# PT4115_LED_Driver.net
KiCad netlist of a schematic drawn in EAGLE
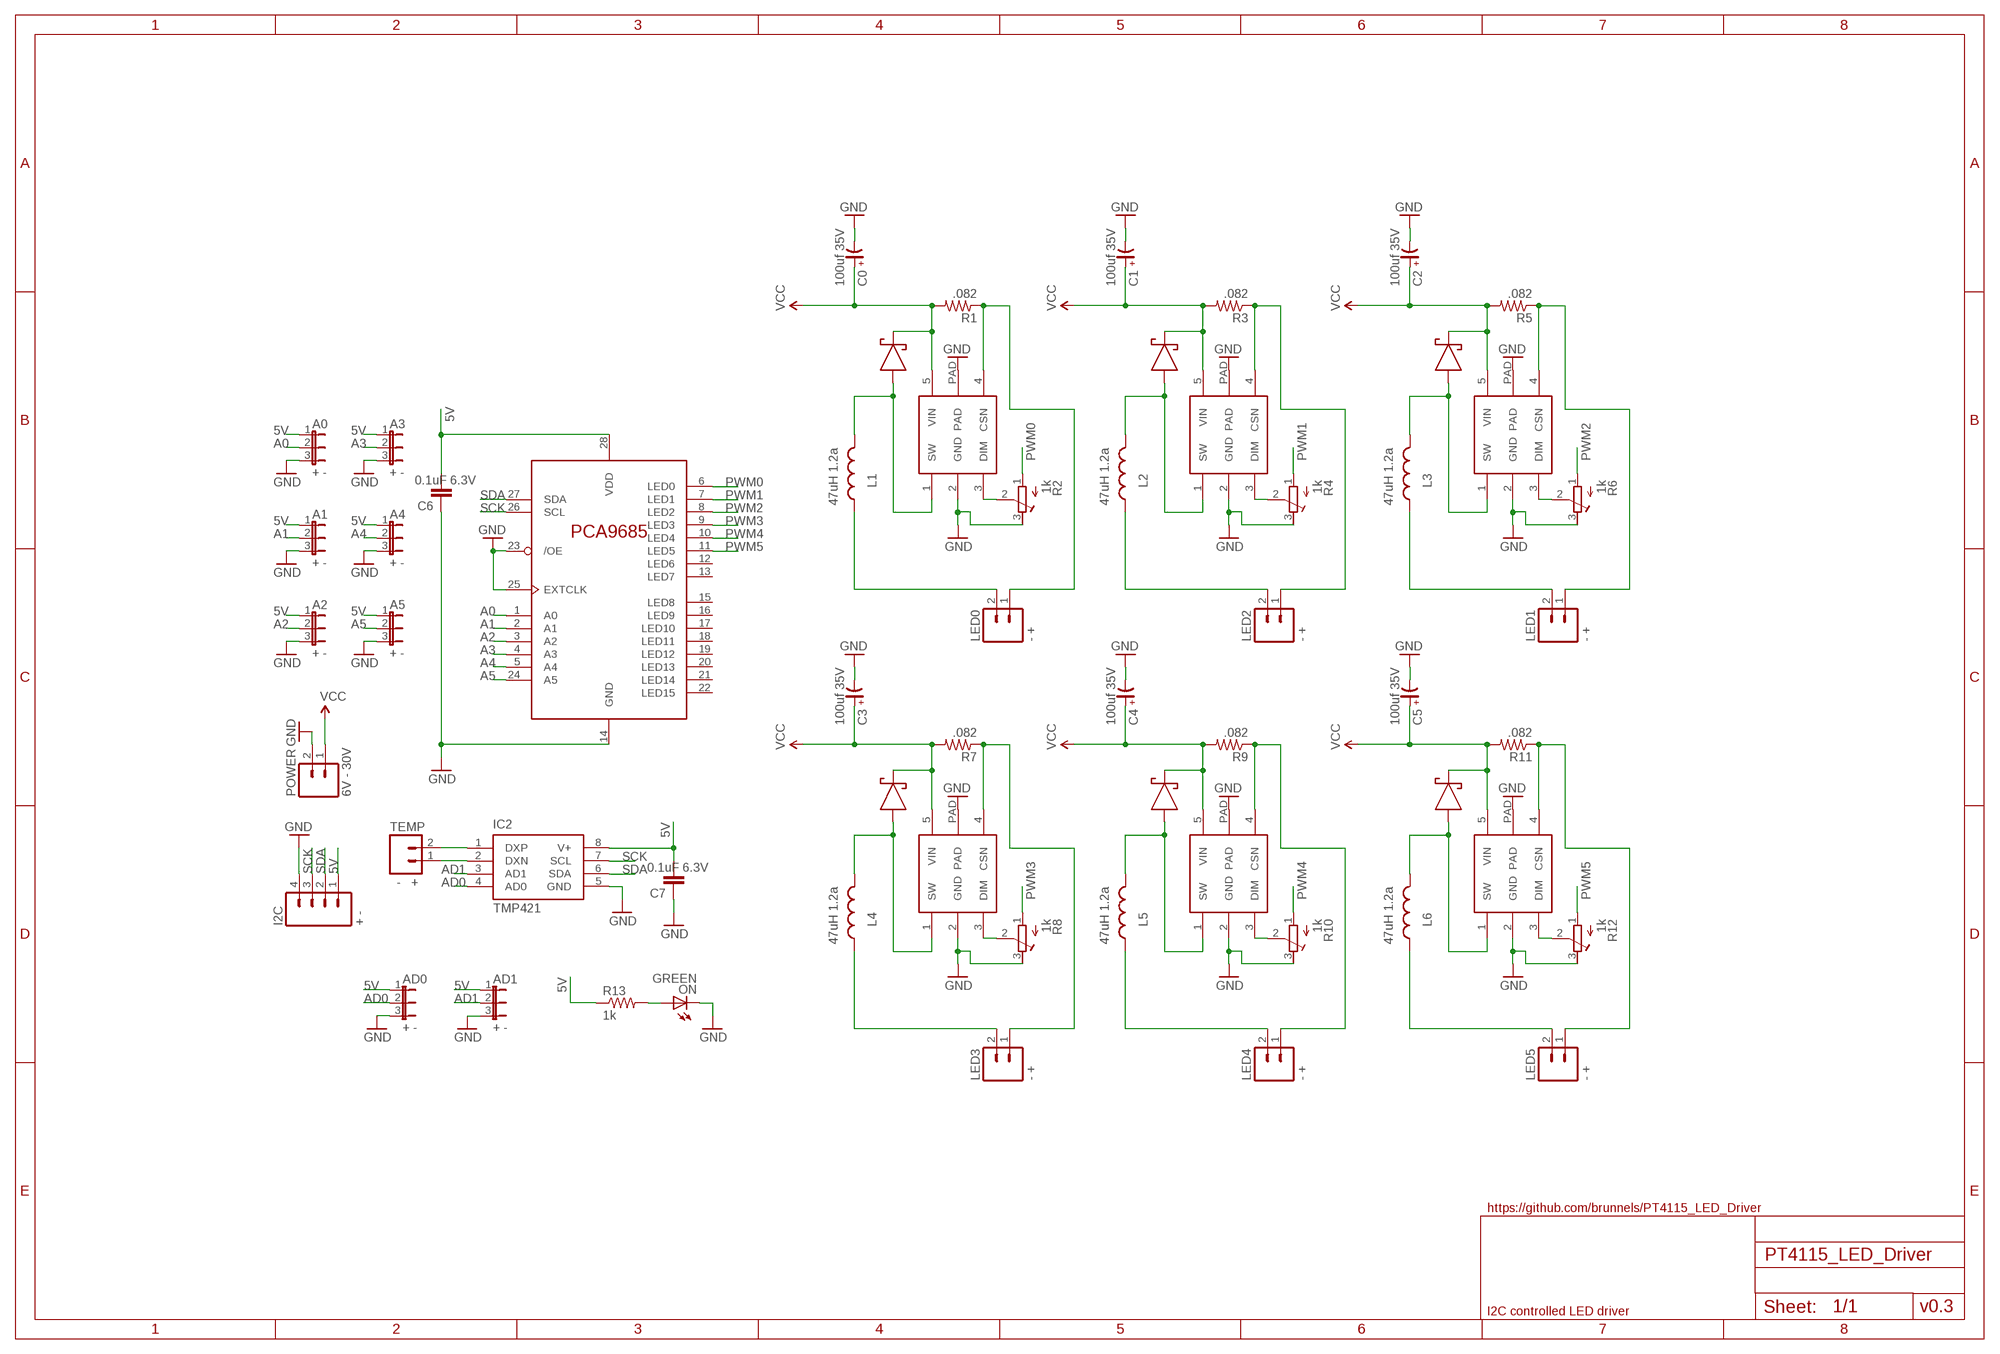
[diagram p0: schematic, sheet 1]

(export (version "E")
  (design (tool "Eeschema 10.0.6"))
  (components
    (comp (ref "A0")
      (value "+ -")
      (footprint "eagle-import:SJ_3")
      (libsource (lib "eagle-import") (part "JUMPER-3SMD"))
    )
    (comp (ref "A1")
      (value "+ -")
      (footprint "eagle-import:SJ_3")
      (libsource (lib "eagle-import") (part "JUMPER-3SMD"))
    )
    (comp (ref "A2")
      (value "+ -")
      (footprint "eagle-import:SJ_3")
      (libsource (lib "eagle-import") (part "JUMPER-3SMD"))
    )
    (comp (ref "A3")
      (value "+ -")
      (footprint "eagle-import:SJ_3")
      (libsource (lib "eagle-import") (part "JUMPER-3SMD"))
    )
    (comp (ref "A4")
      (value "+ -")
      (footprint "eagle-import:SJ_3")
      (libsource (lib "eagle-import") (part "JUMPER-3SMD"))
    )
    (comp (ref "A5")
      (value "+ -")
      (footprint "eagle-import:SJ_3")
      (libsource (lib "eagle-import") (part "JUMPER-3SMD"))
    )
    (comp (ref "AD0")
      (value "+ -")
      (footprint "eagle-import:SJ_3")
      (libsource (lib "eagle-import") (part "JUMPER-3SMD"))
    )
    (comp (ref "AD1")
      (value "+ -")
      (footprint "eagle-import:SJ_3")
      (libsource (lib "eagle-import") (part "JUMPER-3SMD"))
    )
    (comp (ref "C0")
      (value "100uf 35V")
      (footprint "eagle-import:CSV-E_F")
      (libsource (lib "eagle-import") (part "CP_SV-E/F"))
    )
    (comp (ref "C1")
      (value "100uf 35V")
      (footprint "eagle-import:CSV-E_F")
      (libsource (lib "eagle-import") (part "CP_SV-E/F"))
    )
    (comp (ref "C2")
      (value "100uf 35V")
      (footprint "eagle-import:CSV-E_F")
      (libsource (lib "eagle-import") (part "CP_SV-E/F"))
    )
    (comp (ref "C3")
      (value "100uf 35V")
      (footprint "eagle-import:CSV-E_F")
      (libsource (lib "eagle-import") (part "CP_SV-E/F"))
    )
    (comp (ref "C4")
      (value "100uf 35V")
      (footprint "eagle-import:CSV-E_F")
      (libsource (lib "eagle-import") (part "CP_SV-E/F"))
    )
    (comp (ref "C5")
      (value "100uf 35V")
      (footprint "eagle-import:CSV-E_F")
      (libsource (lib "eagle-import") (part "CP_SV-E/F"))
    )
    (comp (ref "C6")
      (value "0.1uF 6.3V")
      (footprint "eagle-import:0805")
      (libsource (lib "eagle-import") (part "CAP0805"))
    )
    (comp (ref "C7")
      (value "0.1uF 6.3V")
      (footprint "eagle-import:0805")
      (libsource (lib "eagle-import") (part "CAP0805"))
    )
    (comp (ref "D1")
      (value "SCHOTTKY_DIODE-SS18")
      (footprint "eagle-import:DO-214")
      (libsource (lib "eagle-import") (part "SCHOTTKY_DIODE-SS18"))
    )
    (comp (ref "D2")
      (value "SCHOTTKY_DIODE-SS18")
      (footprint "eagle-import:DO-214")
      (libsource (lib "eagle-import") (part "SCHOTTKY_DIODE-SS18"))
    )
    (comp (ref "D3")
      (value "SCHOTTKY_DIODE-SS18")
      (footprint "eagle-import:DO-214")
      (libsource (lib "eagle-import") (part "SCHOTTKY_DIODE-SS18"))
    )
    (comp (ref "D4")
      (value "SCHOTTKY_DIODE-SS18")
      (footprint "eagle-import:DO-214")
      (libsource (lib "eagle-import") (part "SCHOTTKY_DIODE-SS18"))
    )
    (comp (ref "D5")
      (value "SCHOTTKY_DIODE-SS18")
      (footprint "eagle-import:DO-214")
      (libsource (lib "eagle-import") (part "SCHOTTKY_DIODE-SS18"))
    )
    (comp (ref "D6")
      (value "SCHOTTKY_DIODE-SS18")
      (footprint "eagle-import:DO-214")
      (libsource (lib "eagle-import") (part "SCHOTTKY_DIODE-SS18"))
    )
    (comp (ref "DRV0")
      (value "PT4115")
      (footprint "eagle-import:SOT89-5")
      (libsource (lib "eagle-import") (part "PT4115"))
    )
    (comp (ref "DRV1")
      (value "PT4115")
      (footprint "eagle-import:SOT89-5")
      (libsource (lib "eagle-import") (part "PT4115"))
    )
    (comp (ref "DRV2")
      (value "PT4115")
      (footprint "eagle-import:SOT89-5")
      (libsource (lib "eagle-import") (part "PT4115"))
    )
    (comp (ref "DRV3")
      (value "PT4115")
      (footprint "eagle-import:SOT89-5")
      (libsource (lib "eagle-import") (part "PT4115"))
    )
    (comp (ref "DRV4")
      (value "PT4115")
      (footprint "eagle-import:SOT89-5")
      (libsource (lib "eagle-import") (part "PT4115"))
    )
    (comp (ref "DRV5")
      (value "PT4115")
      (footprint "eagle-import:SOT89-5")
      (libsource (lib "eagle-import") (part "PT4115"))
    )
    (comp (ref "I2C")
      (value "+ -")
      (footprint "eagle-import:MOLEX-1X4")
      (libsource (lib "eagle-import") (part "M04POLAR"))
    )
    (comp (ref "IC1")
      (value "PCA9685PW")
      (footprint "eagle-import:TSSOP28")
      (libsource (lib "eagle-import") (part "PCA9685PW"))
    )
    (comp (ref "IC2")
      (value "TMP421")
      (footprint "eagle-import:SOT23-8")
      (libsource (lib "eagle-import") (part "TMP421"))
    )
    (comp (ref "L1")
      (value "47uH 1.2a")
      (footprint "eagle-import:CR54")
      (libsource (lib "eagle-import") (part "INDUCTORCR54"))
    )
    (comp (ref "L2")
      (value "47uH 1.2a")
      (footprint "eagle-import:CR54")
      (libsource (lib "eagle-import") (part "INDUCTORCR54"))
    )
    (comp (ref "L3")
      (value "47uH 1.2a")
      (footprint "eagle-import:CR54")
      (libsource (lib "eagle-import") (part "INDUCTORCR54"))
    )
    (comp (ref "L4")
      (value "47uH 1.2a")
      (footprint "eagle-import:CR54")
      (libsource (lib "eagle-import") (part "INDUCTORCR54"))
    )
    (comp (ref "L5")
      (value "47uH 1.2a")
      (footprint "eagle-import:CR54")
      (libsource (lib "eagle-import") (part "INDUCTORCR54"))
    )
    (comp (ref "L6")
      (value "47uH 1.2a")
      (footprint "eagle-import:CR54")
      (libsource (lib "eagle-import") (part "INDUCTORCR54"))
    )
    (comp (ref "LED0")
      (value "- +")
      (footprint "eagle-import:SCREWTERMINAL-3.5MM-2")
      (libsource (lib "eagle-import") (part "M023.5MM"))
    )
    (comp (ref "LED1")
      (value "- +")
      (footprint "eagle-import:SCREWTERMINAL-3.5MM-2")
      (libsource (lib "eagle-import") (part "M023.5MM"))
    )
    (comp (ref "LED2")
      (value "- +")
      (footprint "eagle-import:SCREWTERMINAL-3.5MM-2")
      (libsource (lib "eagle-import") (part "M023.5MM"))
    )
    (comp (ref "LED3")
      (value "- +")
      (footprint "eagle-import:SCREWTERMINAL-3.5MM-2")
      (libsource (lib "eagle-import") (part "M023.5MM"))
    )
    (comp (ref "LED4")
      (value "- +")
      (footprint "eagle-import:SCREWTERMINAL-3.5MM-2")
      (libsource (lib "eagle-import") (part "M023.5MM"))
    )
    (comp (ref "LED5")
      (value "- +")
      (footprint "eagle-import:SCREWTERMINAL-3.5MM-2")
      (libsource (lib "eagle-import") (part "M023.5MM"))
    )
    (comp (ref "ON")
      (value "GREEN")
      (footprint "eagle-import:CHIPLED_0805")
      (libsource (lib "eagle-import") (part "LEDCHIPLED_0805"))
    )
    (comp (ref "POWER")
      (value "6V - 30V")
      (footprint "eagle-import:SCREWTERMINAL-3.5MM-2")
      (libsource (lib "eagle-import") (part "M023.5MM"))
    )
    (comp (ref "R1")
      (value ".082")
      (footprint "eagle-import:1206")
      (libsource (lib "eagle-import") (part "RESISTOR1206"))
    )
    (comp (ref "R2")
      (value "1k")
      (footprint "eagle-import:RTRIM3296W")
      (libsource (lib "eagle-import") (part "R-TRIMM3296W"))
    )
    (comp (ref "R3")
      (value ".082")
      (footprint "eagle-import:1206")
      (libsource (lib "eagle-import") (part "RESISTOR1206"))
    )
    (comp (ref "R4")
      (value "1k")
      (footprint "eagle-import:RTRIM3296W")
      (libsource (lib "eagle-import") (part "R-TRIMM3296W"))
    )
    (comp (ref "R5")
      (value ".082")
      (footprint "eagle-import:1206")
      (libsource (lib "eagle-import") (part "RESISTOR1206"))
    )
    (comp (ref "R6")
      (value "1k")
      (footprint "eagle-import:RTRIM3296W")
      (libsource (lib "eagle-import") (part "R-TRIMM3296W"))
    )
    (comp (ref "R7")
      (value ".082")
      (footprint "eagle-import:1206")
      (libsource (lib "eagle-import") (part "RESISTOR1206"))
    )
    (comp (ref "R8")
      (value "1k")
      (footprint "eagle-import:RTRIM3296W")
      (libsource (lib "eagle-import") (part "R-TRIMM3296W"))
    )
    (comp (ref "R9")
      (value ".082")
      (footprint "eagle-import:1206")
      (libsource (lib "eagle-import") (part "RESISTOR1206"))
    )
    (comp (ref "R10")
      (value "1k")
      (footprint "eagle-import:RTRIM3296W")
      (libsource (lib "eagle-import") (part "R-TRIMM3296W"))
    )
    (comp (ref "R11")
      (value ".082")
      (footprint "eagle-import:1206")
      (libsource (lib "eagle-import") (part "RESISTOR1206"))
    )
    (comp (ref "R12")
      (value "1k")
      (footprint "eagle-import:RTRIM3296W")
      (libsource (lib "eagle-import") (part "R-TRIMM3296W"))
    )
    (comp (ref "R13")
      (value "1k")
      (footprint "eagle-import:0603-RES")
      (libsource (lib "eagle-import") (part "SparkFun_RESISTOR0603-RES"))
    )
    (comp (ref "TEMP")
      (value "- +")
      (footprint "eagle-import:1X02")
      (libsource (lib "eagle-import") (part "M02PTH"))
    )
  )
  (nets
    (net (code "1") (name "/5V") (class "Default")
      (node (ref "A0") (pin "1") (pinfunction "1_1") (pintype "passive"))
      (node (ref "A1") (pin "1") (pinfunction "1_1") (pintype "passive"))
      (node (ref "A2") (pin "1") (pinfunction "1_1") (pintype "passive"))
      (node (ref "A3") (pin "1") (pinfunction "1_1") (pintype "passive"))
      (node (ref "A4") (pin "1") (pinfunction "1_1") (pintype "passive"))
      (node (ref "A5") (pin "1") (pinfunction "1_1") (pintype "passive"))
      (node (ref "AD0") (pin "1") (pinfunction "1_1") (pintype "passive"))
      (node (ref "AD1") (pin "1") (pinfunction "1_1") (pintype "passive"))
      (node (ref "C6") (pin "2") (pinfunction "2_2") (pintype "passive"))
      (node (ref "C7") (pin "2") (pinfunction "2_2") (pintype "passive"))
      (node (ref "I2C") (pin "1") (pinfunction "1_1") (pintype "passive"))
      (node (ref "IC1") (pin "28") (pinfunction "VDD_28") (pintype "power_in"))
      (node (ref "IC2") (pin "8") (pinfunction "V+_8") (pintype "bidirectional"))
      (node (ref "R13") (pin "1") (pinfunction "1_1") (pintype "passive"))
    )
    (net (code "2") (name "/A0") (class "Default")
      (node (ref "A0") (pin "2") (pinfunction "2_2") (pintype "passive"))
      (node (ref "IC1") (pin "1") (pinfunction "A0_1") (pintype "bidirectional"))
    )
    (net (code "3") (name "/A1") (class "Default")
      (node (ref "A1") (pin "2") (pinfunction "2_2") (pintype "passive"))
      (node (ref "IC1") (pin "2") (pinfunction "A1_2") (pintype "bidirectional"))
    )
    (net (code "4") (name "/A2") (class "Default")
      (node (ref "A2") (pin "2") (pinfunction "2_2") (pintype "passive"))
      (node (ref "IC1") (pin "3") (pinfunction "A2_3") (pintype "bidirectional"))
    )
    (net (code "5") (name "/A3") (class "Default")
      (node (ref "A3") (pin "2") (pinfunction "2_2") (pintype "passive"))
      (node (ref "IC1") (pin "4") (pinfunction "A3_4") (pintype "bidirectional"))
    )
    (net (code "6") (name "/A4") (class "Default")
      (node (ref "A4") (pin "2") (pinfunction "2_2") (pintype "passive"))
      (node (ref "IC1") (pin "5") (pinfunction "A4_5") (pintype "bidirectional"))
    )
    (net (code "7") (name "/A5") (class "Default")
      (node (ref "A5") (pin "2") (pinfunction "2_2") (pintype "passive"))
      (node (ref "IC1") (pin "24") (pinfunction "A5_24") (pintype "bidirectional"))
    )
    (net (code "8") (name "/AD0") (class "Default")
      (node (ref "AD0") (pin "2") (pinfunction "2_2") (pintype "passive"))
      (node (ref "IC2") (pin "4") (pinfunction "AD0_4") (pintype "bidirectional"))
    )
    (net (code "9") (name "/AD1") (class "Default")
      (node (ref "AD1") (pin "2") (pinfunction "2_2") (pintype "passive"))
      (node (ref "IC2") (pin "3") (pinfunction "AD1_3") (pintype "bidirectional"))
    )
    (net (code "10") (name "/PWM0") (class "Default")
      (node (ref "IC1") (pin "6") (pinfunction "LED0_6") (pintype "bidirectional"))
      (node (ref "R2") (pin "1") (pinfunction "E_1") (pintype "passive"))
    )
    (net (code "11") (name "/PWM1") (class "Default")
      (node (ref "IC1") (pin "7") (pinfunction "LED1_7") (pintype "bidirectional"))
      (node (ref "R4") (pin "1") (pinfunction "E_1") (pintype "passive"))
    )
    (net (code "12") (name "/PWM2") (class "Default")
      (node (ref "IC1") (pin "8") (pinfunction "LED2_8") (pintype "bidirectional"))
      (node (ref "R6") (pin "1") (pinfunction "E_1") (pintype "passive"))
    )
    (net (code "13") (name "/PWM3") (class "Default")
      (node (ref "IC1") (pin "9") (pinfunction "LED3_9") (pintype "bidirectional"))
      (node (ref "R8") (pin "1") (pinfunction "E_1") (pintype "passive"))
    )
    (net (code "14") (name "/PWM4") (class "Default")
      (node (ref "IC1") (pin "10") (pinfunction "LED4_10") (pintype "bidirectional"))
      (node (ref "R10") (pin "1") (pinfunction "E_1") (pintype "passive"))
    )
    (net (code "15") (name "/PWM5") (class "Default")
      (node (ref "IC1") (pin "11") (pinfunction "LED5_11") (pintype "bidirectional"))
      (node (ref "R12") (pin "1") (pinfunction "E_1") (pintype "passive"))
    )
    (net (code "16") (name "/SCK") (class "Default")
      (node (ref "I2C") (pin "3") (pinfunction "3_3") (pintype "passive"))
      (node (ref "IC1") (pin "26") (pinfunction "SCL_26") (pintype "bidirectional"))
      (node (ref "IC2") (pin "7") (pinfunction "SCL_7") (pintype "bidirectional"))
    )
    (net (code "17") (name "/SDA") (class "Default")
      (node (ref "I2C") (pin "2") (pinfunction "2_2") (pintype "passive"))
      (node (ref "IC1") (pin "27") (pinfunction "SDA_27") (pintype "bidirectional"))
      (node (ref "IC2") (pin "6") (pinfunction "SDA_6") (pintype "bidirectional"))
    )
    (net (code "18") (name "GND") (class "Default")
      (node (ref "A0") (pin "3") (pinfunction "3_3") (pintype "passive"))
      (node (ref "A1") (pin "3") (pinfunction "3_3") (pintype "passive"))
      (node (ref "A2") (pin "3") (pinfunction "3_3") (pintype "passive"))
      (node (ref "A3") (pin "3") (pinfunction "3_3") (pintype "passive"))
      (node (ref "A4") (pin "3") (pinfunction "3_3") (pintype "passive"))
      (node (ref "A5") (pin "3") (pinfunction "3_3") (pintype "passive"))
      (node (ref "AD0") (pin "3") (pinfunction "3_3") (pintype "passive"))
      (node (ref "AD1") (pin "3") (pinfunction "3_3") (pintype "passive"))
      (node (ref "C0") (pin "-") (pinfunction "-_-") (pintype "passive"))
      (node (ref "C1") (pin "-") (pinfunction "-_-") (pintype "passive"))
      (node (ref "C2") (pin "-") (pinfunction "-_-") (pintype "passive"))
      (node (ref "C3") (pin "-") (pinfunction "-_-") (pintype "passive"))
      (node (ref "C4") (pin "-") (pinfunction "-_-") (pintype "passive"))
      (node (ref "C5") (pin "-") (pinfunction "-_-") (pintype "passive"))
      (node (ref "C6") (pin "1") (pinfunction "1_1") (pintype "passive"))
      (node (ref "C7") (pin "1") (pinfunction "1_1") (pintype "passive"))
      (node (ref "DRV0") (pin "2") (pinfunction "GND_2") (pintype "bidirectional"))
      (node (ref "DRV0") (pin "PAD") (pinfunction "PAD_PAD") (pintype "bidirectional"))
      (node (ref "DRV1") (pin "2") (pinfunction "GND_2") (pintype "bidirectional"))
      (node (ref "DRV1") (pin "PAD") (pinfunction "PAD_PAD") (pintype "bidirectional"))
      (node (ref "DRV2") (pin "2") (pinfunction "GND_2") (pintype "bidirectional"))
      (node (ref "DRV2") (pin "PAD") (pinfunction "PAD_PAD") (pintype "bidirectional"))
      (node (ref "DRV3") (pin "2") (pinfunction "GND_2") (pintype "bidirectional"))
      (node (ref "DRV3") (pin "PAD") (pinfunction "PAD_PAD") (pintype "bidirectional"))
      (node (ref "DRV4") (pin "2") (pinfunction "GND_2") (pintype "bidirectional"))
      (node (ref "DRV4") (pin "PAD") (pinfunction "PAD_PAD") (pintype "bidirectional"))
      (node (ref "DRV5") (pin "2") (pinfunction "GND_2") (pintype "bidirectional"))
      (node (ref "DRV5") (pin "PAD") (pinfunction "PAD_PAD") (pintype "bidirectional"))
      (node (ref "I2C") (pin "4") (pinfunction "4_4") (pintype "passive"))
      (node (ref "IC1") (pin "14") (pinfunction "GND_14") (pintype "power_in"))
      (node (ref "IC1") (pin "23") (pinfunction "/OE_23") (pintype "bidirectional"))
      (node (ref "IC1") (pin "25") (pinfunction "EXTCLK_25") (pintype "input"))
      (node (ref "IC2") (pin "5") (pinfunction "GND_5") (pintype "bidirectional"))
      (node (ref "ON") (pin "C") (pinfunction "C_C") (pintype "passive"))
      (node (ref "POWER") (pin "2") (pinfunction "2_2") (pintype "passive"))
      (node (ref "R10") (pin "3") (pinfunction "A_3") (pintype "passive"))
      (node (ref "R12") (pin "3") (pinfunction "A_3") (pintype "passive"))
      (node (ref "R2") (pin "3") (pinfunction "A_3") (pintype "passive"))
      (node (ref "R4") (pin "3") (pinfunction "A_3") (pintype "passive"))
      (node (ref "R6") (pin "3") (pinfunction "A_3") (pintype "passive"))
      (node (ref "R8") (pin "3") (pinfunction "A_3") (pintype "passive"))
    )
    (net (code "19") (name "Net-(D1-ANODE)") (class "Default")
      (node (ref "D1") (pin "P$2") (pinfunction "ANODE_P$2") (pintype "bidirectional"))
      (node (ref "DRV1") (pin "1") (pinfunction "SW_1") (pintype "bidirectional"))
      (node (ref "L2") (pin "P$2") (pinfunction "2_P$2") (pintype "passive"))
    )
    (net (code "20") (name "Net-(D2-ANODE)") (class "Default")
      (node (ref "D2") (pin "P$2") (pinfunction "ANODE_P$2") (pintype "bidirectional"))
      (node (ref "DRV2") (pin "1") (pinfunction "SW_1") (pintype "bidirectional"))
      (node (ref "L3") (pin "P$2") (pinfunction "2_P$2") (pintype "passive"))
    )
    (net (code "21") (name "Net-(D3-ANODE)") (class "Default")
      (node (ref "D3") (pin "P$2") (pinfunction "ANODE_P$2") (pintype "bidirectional"))
      (node (ref "DRV0") (pin "1") (pinfunction "SW_1") (pintype "bidirectional"))
      (node (ref "L1") (pin "P$2") (pinfunction "2_P$2") (pintype "passive"))
    )
    (net (code "22") (name "Net-(D4-ANODE)") (class "Default")
      (node (ref "D4") (pin "P$2") (pinfunction "ANODE_P$2") (pintype "bidirectional"))
      (node (ref "DRV3") (pin "1") (pinfunction "SW_1") (pintype "bidirectional"))
      (node (ref "L4") (pin "P$2") (pinfunction "2_P$2") (pintype "passive"))
    )
    (net (code "23") (name "Net-(D5-ANODE)") (class "Default")
      (node (ref "D5") (pin "P$2") (pinfunction "ANODE_P$2") (pintype "bidirectional"))
      (node (ref "DRV4") (pin "1") (pinfunction "SW_1") (pintype "bidirectional"))
      (node (ref "L5") (pin "P$2") (pinfunction "2_P$2") (pintype "passive"))
    )
    (net (code "24") (name "Net-(D6-ANODE)") (class "Default")
      (node (ref "D6") (pin "P$2") (pinfunction "ANODE_P$2") (pintype "bidirectional"))
      (node (ref "DRV5") (pin "1") (pinfunction "SW_1") (pintype "bidirectional"))
      (node (ref "L6") (pin "P$2") (pinfunction "2_P$2") (pintype "passive"))
    )
    (net (code "25") (name "Net-(DRV0-CSN)") (class "Default")
      (node (ref "DRV0") (pin "4") (pinfunction "CSN_4") (pintype "bidirectional"))
      (node (ref "LED0") (pin "1") (pinfunction "1_1") (pintype "passive"))
      (node (ref "R1") (pin "1") (pinfunction "1_1") (pintype "passive"))
    )
    (net (code "26") (name "Net-(DRV0-DIM)") (class "Default")
      (node (ref "DRV0") (pin "3") (pinfunction "DIM_3") (pintype "bidirectional"))
      (node (ref "R2") (pin "2") (pinfunction "S_2") (pintype "passive"))
    )
    (net (code "27") (name "Net-(DRV1-CSN)") (class "Default")
      (node (ref "DRV1") (pin "4") (pinfunction "CSN_4") (pintype "bidirectional"))
      (node (ref "LED2") (pin "1") (pinfunction "1_1") (pintype "passive"))
      (node (ref "R3") (pin "1") (pinfunction "1_1") (pintype "passive"))
    )
    (net (code "28") (name "Net-(DRV1-DIM)") (class "Default")
      (node (ref "DRV1") (pin "3") (pinfunction "DIM_3") (pintype "bidirectional"))
      (node (ref "R4") (pin "2") (pinfunction "S_2") (pintype "passive"))
    )
    (net (code "29") (name "Net-(DRV2-CSN)") (class "Default")
      (node (ref "DRV2") (pin "4") (pinfunction "CSN_4") (pintype "bidirectional"))
      (node (ref "LED1") (pin "1") (pinfunction "1_1") (pintype "passive"))
      (node (ref "R5") (pin "1") (pinfunction "1_1") (pintype "passive"))
    )
    (net (code "30") (name "Net-(DRV2-DIM)") (class "Default")
      (node (ref "DRV2") (pin "3") (pinfunction "DIM_3") (pintype "bidirectional"))
      (node (ref "R6") (pin "2") (pinfunction "S_2") (pintype "passive"))
    )
    (net (code "31") (name "Net-(DRV3-CSN)") (class "Default")
      (node (ref "DRV3") (pin "4") (pinfunction "CSN_4") (pintype "bidirectional"))
      (node (ref "LED3") (pin "1") (pinfunction "1_1") (pintype "passive"))
      (node (ref "R7") (pin "1") (pinfunction "1_1") (pintype "passive"))
    )
    (net (code "32") (name "Net-(DRV3-DIM)") (class "Default")
      (node (ref "DRV3") (pin "3") (pinfunction "DIM_3") (pintype "bidirectional"))
      (node (ref "R8") (pin "2") (pinfunction "S_2") (pintype "passive"))
    )
    (net (code "33") (name "Net-(DRV4-CSN)") (class "Default")
      (node (ref "DRV4") (pin "4") (pinfunction "CSN_4") (pintype "bidirectional"))
      (node (ref "LED4") (pin "1") (pinfunction "1_1") (pintype "passive"))
      (node (ref "R9") (pin "1") (pinfunction "1_1") (pintype "passive"))
    )
    (net (code "34") (name "Net-(DRV4-DIM)") (class "Default")
      (node (ref "DRV4") (pin "3") (pinfunction "DIM_3") (pintype "bidirectional"))
      (node (ref "R10") (pin "2") (pinfunction "S_2") (pintype "passive"))
    )
    (net (code "35") (name "Net-(DRV5-CSN)") (class "Default")
      (node (ref "DRV5") (pin "4") (pinfunction "CSN_4") (pintype "bidirectional"))
      (node (ref "LED5") (pin "1") (pinfunction "1_1") (pintype "passive"))
      (node (ref "R11") (pin "1") (pinfunction "1_1") (pintype "passive"))
    )
    (net (code "36") (name "Net-(DRV5-DIM)") (class "Default")
      (node (ref "DRV5") (pin "3") (pinfunction "DIM_3") (pintype "bidirectional"))
      (node (ref "R12") (pin "2") (pinfunction "S_2") (pintype "passive"))
    )
    (net (code "37") (name "Net-(IC2-DXN)") (class "Default")
      (node (ref "IC2") (pin "2") (pinfunction "DXN_2") (pintype "bidirectional"))
      (node (ref "TEMP") (pin "1") (pinfunction "1_1") (pintype "passive"))
    )
    (net (code "38") (name "Net-(IC2-DXP)") (class "Default")
      (node (ref "IC2") (pin "1") (pinfunction "DXP_1") (pintype "bidirectional"))
      (node (ref "TEMP") (pin "2") (pinfunction "2_2") (pintype "passive"))
    )
    (net (code "39") (name "Net-(L1-1)") (class "Default")
      (node (ref "L1") (pin "P$1") (pinfunction "1_P$1") (pintype "passive"))
      (node (ref "LED0") (pin "2") (pinfunction "2_2") (pintype "passive"))
    )
    (net (code "40") (name "Net-(L2-1)") (class "Default")
      (node (ref "L2") (pin "P$1") (pinfunction "1_P$1") (pintype "passive"))
      (node (ref "LED2") (pin "2") (pinfunction "2_2") (pintype "passive"))
    )
    (net (code "41") (name "Net-(L3-1)") (class "Default")
      (node (ref "L3") (pin "P$1") (pinfunction "1_P$1") (pintype "passive"))
      (node (ref "LED1") (pin "2") (pinfunction "2_2") (pintype "passive"))
    )
    (net (code "42") (name "Net-(L4-1)") (class "Default")
      (node (ref "L4") (pin "P$1") (pinfunction "1_P$1") (pintype "passive"))
      (node (ref "LED3") (pin "2") (pinfunction "2_2") (pintype "passive"))
    )
    (net (code "43") (name "Net-(L5-1)") (class "Default")
      (node (ref "L5") (pin "P$1") (pinfunction "1_P$1") (pintype "passive"))
      (node (ref "LED4") (pin "2") (pinfunction "2_2") (pintype "passive"))
    )
    (net (code "44") (name "Net-(L6-1)") (class "Default")
      (node (ref "L6") (pin "P$1") (pinfunction "1_P$1") (pintype "passive"))
      (node (ref "LED5") (pin "2") (pinfunction "2_2") (pintype "passive"))
    )
    (net (code "45") (name "Net-(ON-PadA)") (class "Default")
      (node (ref "ON") (pin "A") (pinfunction "A_A") (pintype "passive"))
      (node (ref "R13") (pin "2") (pinfunction "2_2") (pintype "passive"))
    )
    (net (code "46") (name "VCC") (class "Default")
      (node (ref "C0") (pin "+") (pinfunction "+_+") (pintype "passive"))
      (node (ref "C1") (pin "+") (pinfunction "+_+") (pintype "passive"))
      (node (ref "C2") (pin "+") (pinfunction "+_+") (pintype "passive"))
      (node (ref "C3") (pin "+") (pinfunction "+_+") (pintype "passive"))
      (node (ref "C4") (pin "+") (pinfunction "+_+") (pintype "passive"))
      (node (ref "C5") (pin "+") (pinfunction "+_+") (pintype "passive"))
      (node (ref "D1") (pin "P$1") (pinfunction "CATHODE_P$1") (pintype "bidirectional"))
      (node (ref "D2") (pin "P$1") (pinfunction "CATHODE_P$1") (pintype "bidirectional"))
      (node (ref "D3") (pin "P$1") (pinfunction "CATHODE_P$1") (pintype "bidirectional"))
      (node (ref "D4") (pin "P$1") (pinfunction "CATHODE_P$1") (pintype "bidirectional"))
      (node (ref "D5") (pin "P$1") (pinfunction "CATHODE_P$1") (pintype "bidirectional"))
      (node (ref "D6") (pin "P$1") (pinfunction "CATHODE_P$1") (pintype "bidirectional"))
      (node (ref "DRV0") (pin "5") (pinfunction "VIN_5") (pintype "bidirectional"))
      (node (ref "DRV1") (pin "5") (pinfunction "VIN_5") (pintype "bidirectional"))
      (node (ref "DRV2") (pin "5") (pinfunction "VIN_5") (pintype "bidirectional"))
      (node (ref "DRV3") (pin "5") (pinfunction "VIN_5") (pintype "bidirectional"))
      (node (ref "DRV4") (pin "5") (pinfunction "VIN_5") (pintype "bidirectional"))
      (node (ref "DRV5") (pin "5") (pinfunction "VIN_5") (pintype "bidirectional"))
      (node (ref "POWER") (pin "1") (pinfunction "1_1") (pintype "passive"))
      (node (ref "R1") (pin "2") (pinfunction "2_2") (pintype "passive"))
      (node (ref "R11") (pin "2") (pinfunction "2_2") (pintype "passive"))
      (node (ref "R3") (pin "2") (pinfunction "2_2") (pintype "passive"))
      (node (ref "R5") (pin "2") (pinfunction "2_2") (pintype "passive"))
      (node (ref "R7") (pin "2") (pinfunction "2_2") (pintype "passive"))
      (node (ref "R9") (pin "2") (pinfunction "2_2") (pintype "passive"))
    )
    (net (code "47") (name "unconnected-(IC1-LED6-Pad12)") (class "Default")
      (node (ref "IC1") (pin "12") (pinfunction "LED6_12") (pintype "bidirectional"))
    )
    (net (code "48") (name "unconnected-(IC1-LED7-Pad13)") (class "Default")
      (node (ref "IC1") (pin "13") (pinfunction "LED7_13") (pintype "bidirectional"))
    )
    (net (code "49") (name "unconnected-(IC1-LED8-Pad15)") (class "Default")
      (node (ref "IC1") (pin "15") (pinfunction "LED8_15") (pintype "bidirectional"))
    )
    (net (code "50") (name "unconnected-(IC1-LED9-Pad16)") (class "Default")
      (node (ref "IC1") (pin "16") (pinfunction "LED9_16") (pintype "bidirectional"))
    )
    (net (code "51") (name "unconnected-(IC1-LED10-Pad17)") (class "Default")
      (node (ref "IC1") (pin "17") (pinfunction "LED10_17") (pintype "bidirectional"))
    )
    (net (code "52") (name "unconnected-(IC1-LED11-Pad18)") (class "Default")
      (node (ref "IC1") (pin "18") (pinfunction "LED11_18") (pintype "bidirectional"))
    )
    (net (code "53") (name "unconnected-(IC1-LED12-Pad19)") (class "Default")
      (node (ref "IC1") (pin "19") (pinfunction "LED12_19") (pintype "bidirectional"))
    )
    (net (code "54") (name "unconnected-(IC1-LED13-Pad20)") (class "Default")
      (node (ref "IC1") (pin "20") (pinfunction "LED13_20") (pintype "bidirectional"))
    )
    (net (code "55") (name "unconnected-(IC1-LED14-Pad21)") (class "Default")
      (node (ref "IC1") (pin "21") (pinfunction "LED14_21") (pintype "bidirectional"))
    )
    (net (code "56") (name "unconnected-(IC1-LED15-Pad22)") (class "Default")
      (node (ref "IC1") (pin "22") (pinfunction "LED15_22") (pintype "bidirectional"))
    )
  )
)
